# stm32f4discovery-daugherboard-v2.net
KiCad netlist of a schematic drawn in EAGLE
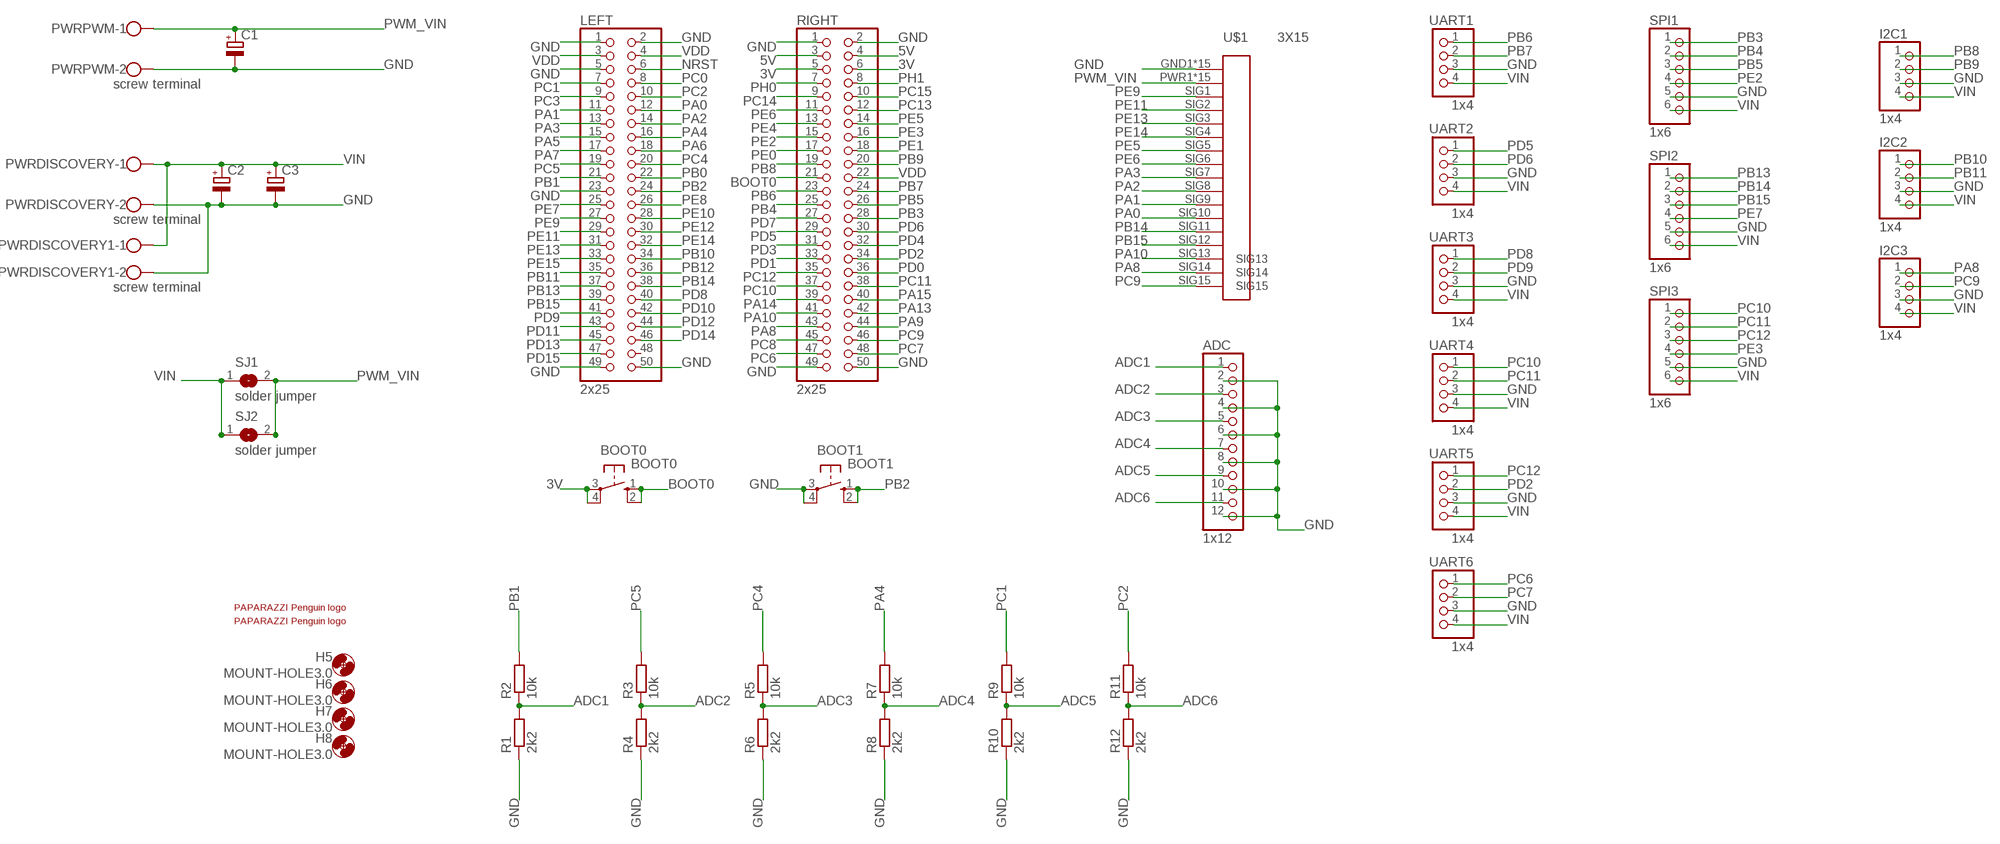
[diagram p0: schematic, sheet 1]

(export (version "E")
  (design (tool "Eeschema 10.0.6"))
  (components
    (comp (ref "ADC")
      (value "1x12")
      (footprint "eagle-import:1X12_90")
      (libsource (lib "eagle-import") (part "PINHD-1X12/90"))
    )
    (comp (ref "BOOT0")
      (value "BOOT0")
      (footprint "eagle-import:B3F-10XX")
      (fields (field (name "MPN") "B3F-1000"))
      (libsource (lib "eagle-import") (part "10-XX"))
    )
    (comp (ref "BOOT1")
      (value "BOOT1")
      (footprint "eagle-import:B3F-10XX")
      (fields (field (name "MPN") "B3F-1000"))
      (libsource (lib "eagle-import") (part "10-XX"))
    )
    (comp (ref "C1")
      (value "CPOL-EU153CLV-0807")
      (footprint "eagle-import:153CLV-0807")
      (libsource (lib "eagle-import") (part "CPOL-EU153CLV-0807"))
    )
    (comp (ref "C2")
      (value "CPOL-EU153CLV-0807")
      (footprint "eagle-import:153CLV-0807")
      (libsource (lib "eagle-import") (part "CPOL-EU153CLV-0807"))
    )
    (comp (ref "C3")
      (value "CPOL-EU153CLV-0807")
      (footprint "eagle-import:153CLV-0807")
      (libsource (lib "eagle-import") (part "CPOL-EU153CLV-0807"))
    )
    (comp (ref "H5")
      (value "MOUNT-HOLE3.0")
      (footprint "eagle-import:3,0")
      (libsource (lib "eagle-import") (part "MOUNT-HOLE3.0"))
    )
    (comp (ref "H6")
      (value "MOUNT-HOLE3.0")
      (footprint "eagle-import:3,0")
      (libsource (lib "eagle-import") (part "MOUNT-HOLE3.0"))
    )
    (comp (ref "H7")
      (value "MOUNT-HOLE3.0")
      (footprint "eagle-import:3,0")
      (libsource (lib "eagle-import") (part "MOUNT-HOLE3.0"))
    )
    (comp (ref "H8")
      (value "MOUNT-HOLE3.0")
      (footprint "eagle-import:3,0")
      (libsource (lib "eagle-import") (part "MOUNT-HOLE3.0"))
    )
    (comp (ref "I2C1")
      (value "1x4")
      (footprint "eagle-import:1X04_90")
      (libsource (lib "eagle-import") (part "PINHD-1X4/90"))
    )
    (comp (ref "I2C2")
      (value "1x4")
      (footprint "eagle-import:1X04_90")
      (libsource (lib "eagle-import") (part "PINHD-1X4/90"))
    )
    (comp (ref "I2C3")
      (value "1x4")
      (footprint "eagle-import:1X04_90")
      (libsource (lib "eagle-import") (part "PINHD-1X4/90"))
    )
    (comp (ref "LEFT")
      (value "2x25")
      (footprint "eagle-import:2X25")
      (libsource (lib "eagle-import") (part "PINHD-2X25"))
    )
    (comp (ref "PWRDISCOVERY")
      (value "screw terminal")
      (footprint "eagle-import:W237-102")
      (fields (field (name "MPN") "237-102"))
      (libsource (lib "eagle-import") (part "W237-102"))
    )
    (comp (ref "PWRDISCOVERY1")
      (value "screw terminal")
      (footprint "eagle-import:W237-102")
      (fields
        (field (name "MPN") "237-102")
        (field (name "MPN_1") "237-102")
        (field (name "OC_FARNELL") "unknown")
        (field (name "OC_NEWARK") "70K9898")
      )
      (libsource (lib "eagle-import") (part "W237-102"))
    )
    (comp (ref "PWRPWM")
      (value "screw terminal")
      (footprint "eagle-import:W237-102")
      (fields (field (name "MPN") "237-102"))
      (libsource (lib "eagle-import") (part "W237-102"))
    )
    (comp (ref "R1")
      (value "2k2")
      (footprint "eagle-import:M0805")
      (libsource (lib "eagle-import") (part "R-EU_M0805"))
    )
    (comp (ref "R2")
      (value "10k")
      (footprint "eagle-import:M0805")
      (libsource (lib "eagle-import") (part "R-EU_M0805"))
    )
    (comp (ref "R3")
      (value "10k")
      (footprint "eagle-import:M0805")
      (libsource (lib "eagle-import") (part "R-EU_M0805"))
    )
    (comp (ref "R4")
      (value "2k2")
      (footprint "eagle-import:M0805")
      (libsource (lib "eagle-import") (part "R-EU_M0805"))
    )
    (comp (ref "R5")
      (value "10k")
      (footprint "eagle-import:M0805")
      (libsource (lib "eagle-import") (part "R-EU_M0805"))
    )
    (comp (ref "R6")
      (value "2k2")
      (footprint "eagle-import:M0805")
      (libsource (lib "eagle-import") (part "R-EU_M0805"))
    )
    (comp (ref "R7")
      (value "10k")
      (footprint "eagle-import:M0805")
      (libsource (lib "eagle-import") (part "R-EU_M0805"))
    )
    (comp (ref "R8")
      (value "2k2")
      (footprint "eagle-import:M0805")
      (libsource (lib "eagle-import") (part "R-EU_M0805"))
    )
    (comp (ref "R9")
      (value "10k")
      (footprint "eagle-import:M0805")
      (libsource (lib "eagle-import") (part "R-EU_M0805"))
    )
    (comp (ref "R10")
      (value "2k2")
      (footprint "eagle-import:M0805")
      (libsource (lib "eagle-import") (part "R-EU_M0805"))
    )
    (comp (ref "R11")
      (value "10k")
      (footprint "eagle-import:M0805")
      (libsource (lib "eagle-import") (part "R-EU_M0805"))
    )
    (comp (ref "R12")
      (value "2k2")
      (footprint "eagle-import:M0805")
      (libsource (lib "eagle-import") (part "R-EU_M0805"))
    )
    (comp (ref "RIGHT")
      (value "2x25")
      (footprint "eagle-import:2X25")
      (libsource (lib "eagle-import") (part "PINHD-2X25"))
    )
    (comp (ref "SJ1")
      (value "solder jumper")
      (footprint "eagle-import:SJW")
      (libsource (lib "eagle-import") (part "SJW"))
    )
    (comp (ref "SJ2")
      (value "solder jumper")
      (footprint "eagle-import:SJW")
      (libsource (lib "eagle-import") (part "SJW"))
    )
    (comp (ref "SPI1")
      (value "1x6")
      (footprint "eagle-import:1X06_90")
      (libsource (lib "eagle-import") (part "PINHD-1X6/90"))
    )
    (comp (ref "SPI2")
      (value "1x6")
      (footprint "eagle-import:1X06_90")
      (libsource (lib "eagle-import") (part "PINHD-1X6/90"))
    )
    (comp (ref "SPI3")
      (value "1x6")
      (footprint "eagle-import:1X06_90")
      (libsource (lib "eagle-import") (part "PINHD-1X6/90"))
    )
    (comp (ref "U$1")
      (value "3X15")
      (footprint "eagle-import:3X15")
      (libsource (lib "eagle-import") (part "3X15"))
    )
    (comp (ref "U$2")
      (value "PAPARAZZI")
      (footprint "eagle-import:PAPARAZZI")
      (libsource (lib "eagle-import") (part "PAPARAZZI"))
    )
    (comp (ref "U$3")
      (value "PAPARAZZI")
      (footprint "eagle-import:PAPARAZZI")
      (libsource (lib "eagle-import") (part "PAPARAZZI"))
    )
    (comp (ref "UART1")
      (value "1x4")
      (footprint "eagle-import:1X04_90")
      (libsource (lib "eagle-import") (part "PINHD-1X4/90"))
    )
    (comp (ref "UART2")
      (value "1x4")
      (footprint "eagle-import:1X04_90")
      (libsource (lib "eagle-import") (part "PINHD-1X4/90"))
    )
    (comp (ref "UART3")
      (value "1x4")
      (footprint "eagle-import:1X04_90")
      (libsource (lib "eagle-import") (part "PINHD-1X4/90"))
    )
    (comp (ref "UART4")
      (value "1x4")
      (footprint "eagle-import:1X04_90")
      (libsource (lib "eagle-import") (part "PINHD-1X4/90"))
    )
    (comp (ref "UART5")
      (value "1x4")
      (footprint "eagle-import:1X04_90")
      (libsource (lib "eagle-import") (part "PINHD-1X4/90"))
    )
    (comp (ref "UART6")
      (value "1x4")
      (footprint "eagle-import:1X04_90")
      (libsource (lib "eagle-import") (part "PINHD-1X4/90"))
    )
  )
  (nets
    (net (code "1") (name "/3V") (class "Default")
      (node (ref "BOOT0") (pin "3") (pinfunction "P_3") (pintype "passive"))
      (node (ref "BOOT0") (pin "4") (pinfunction "P1_4") (pintype "passive"))
      (node (ref "RIGHT") (pin "5") (pinfunction "5_5") (pintype "passive"))
      (node (ref "RIGHT") (pin "6") (pinfunction "6_6") (pintype "passive"))
    )
    (net (code "2") (name "/5V") (class "Default")
      (node (ref "RIGHT") (pin "3") (pinfunction "3_3") (pintype "passive"))
      (node (ref "RIGHT") (pin "4") (pinfunction "4_4") (pintype "passive"))
    )
    (net (code "3") (name "/ADC1") (class "Default")
      (node (ref "ADC") (pin "1") (pinfunction "1_1") (pintype "passive"))
      (node (ref "R1") (pin "2") (pinfunction "2_2") (pintype "passive"))
      (node (ref "R2") (pin "1") (pinfunction "1_1") (pintype "passive"))
    )
    (net (code "4") (name "/ADC2") (class "Default")
      (node (ref "ADC") (pin "3") (pinfunction "3_3") (pintype "passive"))
      (node (ref "R3") (pin "1") (pinfunction "1_1") (pintype "passive"))
      (node (ref "R4") (pin "2") (pinfunction "2_2") (pintype "passive"))
    )
    (net (code "5") (name "/ADC3") (class "Default")
      (node (ref "ADC") (pin "5") (pinfunction "5_5") (pintype "passive"))
      (node (ref "R5") (pin "1") (pinfunction "1_1") (pintype "passive"))
      (node (ref "R6") (pin "2") (pinfunction "2_2") (pintype "passive"))
    )
    (net (code "6") (name "/ADC4") (class "Default")
      (node (ref "ADC") (pin "7") (pinfunction "7_7") (pintype "passive"))
      (node (ref "R7") (pin "1") (pinfunction "1_1") (pintype "passive"))
      (node (ref "R8") (pin "2") (pinfunction "2_2") (pintype "passive"))
    )
    (net (code "7") (name "/ADC5") (class "Default")
      (node (ref "ADC") (pin "9") (pinfunction "9_9") (pintype "passive"))
      (node (ref "R10") (pin "2") (pinfunction "2_2") (pintype "passive"))
      (node (ref "R9") (pin "1") (pinfunction "1_1") (pintype "passive"))
    )
    (net (code "8") (name "/ADC6") (class "Default")
      (node (ref "ADC") (pin "11") (pinfunction "11_11") (pintype "passive"))
      (node (ref "R11") (pin "1") (pinfunction "1_1") (pintype "passive"))
      (node (ref "R12") (pin "2") (pinfunction "2_2") (pintype "passive"))
    )
    (net (code "9") (name "/BOOT0") (class "Default")
      (node (ref "BOOT0") (pin "1") (pinfunction "S_1") (pintype "passive"))
      (node (ref "BOOT0") (pin "2") (pinfunction "S1_2") (pintype "passive"))
      (node (ref "RIGHT") (pin "21") (pinfunction "21_21") (pintype "passive"))
    )
    (net (code "10") (name "/GND") (class "Default")
      (node (ref "ADC") (pin "10") (pinfunction "10_10") (pintype "passive"))
      (node (ref "ADC") (pin "12") (pinfunction "12_12") (pintype "passive"))
      (node (ref "ADC") (pin "2") (pinfunction "2_2") (pintype "passive"))
      (node (ref "ADC") (pin "4") (pinfunction "4_4") (pintype "passive"))
      (node (ref "ADC") (pin "6") (pinfunction "6_6") (pintype "passive"))
      (node (ref "ADC") (pin "8") (pinfunction "8_8") (pintype "passive"))
      (node (ref "BOOT1") (pin "3") (pinfunction "P_3") (pintype "passive"))
      (node (ref "BOOT1") (pin "4") (pinfunction "P1_4") (pintype "passive"))
      (node (ref "C1") (pin "-") (pinfunction "-_-") (pintype "passive"))
      (node (ref "C2") (pin "-") (pinfunction "-_-") (pintype "passive"))
      (node (ref "C3") (pin "-") (pinfunction "-_-") (pintype "passive"))
      (node (ref "I2C1") (pin "3") (pinfunction "3_3") (pintype "passive"))
      (node (ref "I2C2") (pin "3") (pinfunction "3_3") (pintype "passive"))
      (node (ref "I2C3") (pin "3") (pinfunction "3_3") (pintype "passive"))
      (node (ref "LEFT") (pin "1") (pinfunction "1_1") (pintype "passive"))
      (node (ref "LEFT") (pin "2") (pinfunction "2_2") (pintype "passive"))
      (node (ref "LEFT") (pin "23") (pinfunction "23_23") (pintype "passive"))
      (node (ref "LEFT") (pin "49") (pinfunction "49_49") (pintype "passive"))
      (node (ref "LEFT") (pin "5") (pinfunction "5_5") (pintype "passive"))
      (node (ref "LEFT") (pin "50") (pinfunction "50_50") (pintype "passive"))
      (node (ref "PWRDISCOVERY") (pin "2") (pinfunction "KL_2") (pintype "passive"))
      (node (ref "PWRDISCOVERY1") (pin "2") (pinfunction "KL_2") (pintype "passive"))
      (node (ref "PWRPWM") (pin "2") (pinfunction "KL_2") (pintype "passive"))
      (node (ref "R1") (pin "1") (pinfunction "1_1") (pintype "passive"))
      (node (ref "R10") (pin "1") (pinfunction "1_1") (pintype "passive"))
      (node (ref "R12") (pin "1") (pinfunction "1_1") (pintype "passive"))
      (node (ref "R4") (pin "1") (pinfunction "1_1") (pintype "passive"))
      (node (ref "R6") (pin "1") (pinfunction "1_1") (pintype "passive"))
      (node (ref "R8") (pin "1") (pinfunction "1_1") (pintype "passive"))
      (node (ref "RIGHT") (pin "1") (pinfunction "1_1") (pintype "passive"))
      (node (ref "RIGHT") (pin "2") (pinfunction "2_2") (pintype "passive"))
      (node (ref "RIGHT") (pin "49") (pinfunction "49_49") (pintype "passive"))
      (node (ref "RIGHT") (pin "50") (pinfunction "50_50") (pintype "passive"))
      (node (ref "SPI1") (pin "5") (pinfunction "5_5") (pintype "passive"))
      (node (ref "SPI2") (pin "5") (pinfunction "5_5") (pintype "passive"))
      (node (ref "SPI3") (pin "5") (pinfunction "5_5") (pintype "passive"))
      (node (ref "U$1") (pin "GND1") (pinfunction "GND_GND1") (pintype "bidirectional"))
      (node (ref "U$1") (pin "GND10") (pinfunction "GND_GND10") (pintype "bidirectional"))
      (node (ref "U$1") (pin "GND11") (pinfunction "GND_GND11") (pintype "bidirectional"))
      (node (ref "U$1") (pin "GND12") (pinfunction "GND_GND12") (pintype "bidirectional"))
      (node (ref "U$1") (pin "GND13") (pinfunction "GND_GND13") (pintype "bidirectional"))
      (node (ref "U$1") (pin "GND14") (pinfunction "GND_GND14") (pintype "bidirectional"))
      (node (ref "U$1") (pin "GND15") (pinfunction "GND_GND15") (pintype "bidirectional"))
      (node (ref "U$1") (pin "GND2") (pinfunction "GND_GND2") (pintype "bidirectional"))
      (node (ref "U$1") (pin "GND3") (pinfunction "GND_GND3") (pintype "bidirectional"))
      (node (ref "U$1") (pin "GND4") (pinfunction "GND_GND4") (pintype "bidirectional"))
      (node (ref "U$1") (pin "GND5") (pinfunction "GND_GND5") (pintype "bidirectional"))
      (node (ref "U$1") (pin "GND6") (pinfunction "GND_GND6") (pintype "bidirectional"))
      (node (ref "U$1") (pin "GND7") (pinfunction "GND_GND7") (pintype "bidirectional"))
      (node (ref "U$1") (pin "GND8") (pinfunction "GND_GND8") (pintype "bidirectional"))
      (node (ref "U$1") (pin "GND9") (pinfunction "GND_GND9") (pintype "bidirectional"))
      (node (ref "UART1") (pin "3") (pinfunction "3_3") (pintype "passive"))
      (node (ref "UART2") (pin "3") (pinfunction "3_3") (pintype "passive"))
      (node (ref "UART3") (pin "3") (pinfunction "3_3") (pintype "passive"))
      (node (ref "UART4") (pin "3") (pinfunction "3_3") (pintype "passive"))
      (node (ref "UART5") (pin "3") (pinfunction "3_3") (pintype "passive"))
      (node (ref "UART6") (pin "3") (pinfunction "3_3") (pintype "passive"))
    )
    (net (code "11") (name "/NRST") (class "Default")
      (node (ref "LEFT") (pin "6") (pinfunction "6_6") (pintype "passive"))
    )
    (net (code "12") (name "/PA0") (class "Default")
      (node (ref "LEFT") (pin "12") (pinfunction "12_12") (pintype "passive"))
      (node (ref "U$1") (pin "SIG10") (pinfunction "SIG10_SIG10") (pintype "bidirectional"))
    )
    (net (code "13") (name "/PA1") (class "Default")
      (node (ref "LEFT") (pin "11") (pinfunction "11_11") (pintype "passive"))
      (node (ref "U$1") (pin "SIG9") (pinfunction "SIG9_SIG9") (pintype "bidirectional"))
    )
    (net (code "14") (name "/PA2") (class "Default")
      (node (ref "LEFT") (pin "14") (pinfunction "14_14") (pintype "passive"))
      (node (ref "U$1") (pin "SIG8") (pinfunction "SIG8_SIG8") (pintype "bidirectional"))
    )
    (net (code "15") (name "/PA3") (class "Default")
      (node (ref "LEFT") (pin "13") (pinfunction "13_13") (pintype "passive"))
      (node (ref "U$1") (pin "SIG7") (pinfunction "SIG7_SIG7") (pintype "bidirectional"))
    )
    (net (code "16") (name "/PA4") (class "Default")
      (node (ref "LEFT") (pin "16") (pinfunction "16_16") (pintype "passive"))
      (node (ref "R7") (pin "2") (pinfunction "2_2") (pintype "passive"))
    )
    (net (code "17") (name "/PA5") (class "Default")
      (node (ref "LEFT") (pin "15") (pinfunction "15_15") (pintype "passive"))
    )
    (net (code "18") (name "/PA6") (class "Default")
      (node (ref "LEFT") (pin "18") (pinfunction "18_18") (pintype "passive"))
    )
    (net (code "19") (name "/PA7") (class "Default")
      (node (ref "LEFT") (pin "17") (pinfunction "17_17") (pintype "passive"))
    )
    (net (code "20") (name "/PA8") (class "Default")
      (node (ref "I2C3") (pin "1") (pinfunction "1_1") (pintype "passive"))
      (node (ref "RIGHT") (pin "43") (pinfunction "43_43") (pintype "passive"))
      (node (ref "U$1") (pin "SIG14") (pinfunction "SIG14_SIG14") (pintype "bidirectional"))
    )
    (net (code "21") (name "/PA9") (class "Default")
      (node (ref "RIGHT") (pin "44") (pinfunction "44_44") (pintype "passive"))
    )
    (net (code "22") (name "/PA10") (class "Default")
      (node (ref "RIGHT") (pin "41") (pinfunction "41_41") (pintype "passive"))
      (node (ref "U$1") (pin "SIG13") (pinfunction "SIG13_SIG13") (pintype "bidirectional"))
    )
    (net (code "23") (name "/PA13") (class "Default")
      (node (ref "RIGHT") (pin "42") (pinfunction "42_42") (pintype "passive"))
    )
    (net (code "24") (name "/PA14") (class "Default")
      (node (ref "RIGHT") (pin "39") (pinfunction "39_39") (pintype "passive"))
    )
    (net (code "25") (name "/PA15") (class "Default")
      (node (ref "RIGHT") (pin "40") (pinfunction "40_40") (pintype "passive"))
    )
    (net (code "26") (name "/PB0") (class "Default")
      (node (ref "LEFT") (pin "22") (pinfunction "22_22") (pintype "passive"))
    )
    (net (code "27") (name "/PB1") (class "Default")
      (node (ref "LEFT") (pin "21") (pinfunction "21_21") (pintype "passive"))
      (node (ref "R2") (pin "2") (pinfunction "2_2") (pintype "passive"))
    )
    (net (code "28") (name "/PB2") (class "Default")
      (node (ref "BOOT1") (pin "1") (pinfunction "S_1") (pintype "passive"))
      (node (ref "BOOT1") (pin "2") (pinfunction "S1_2") (pintype "passive"))
      (node (ref "LEFT") (pin "24") (pinfunction "24_24") (pintype "passive"))
    )
    (net (code "29") (name "/PB3") (class "Default")
      (node (ref "RIGHT") (pin "28") (pinfunction "28_28") (pintype "passive"))
      (node (ref "SPI1") (pin "1") (pinfunction "1_1") (pintype "passive"))
    )
    (net (code "30") (name "/PB4") (class "Default")
      (node (ref "RIGHT") (pin "25") (pinfunction "25_25") (pintype "passive"))
      (node (ref "SPI1") (pin "2") (pinfunction "2_2") (pintype "passive"))
    )
    (net (code "31") (name "/PB5") (class "Default")
      (node (ref "RIGHT") (pin "26") (pinfunction "26_26") (pintype "passive"))
      (node (ref "SPI1") (pin "3") (pinfunction "3_3") (pintype "passive"))
    )
    (net (code "32") (name "/PB6") (class "Default")
      (node (ref "RIGHT") (pin "23") (pinfunction "23_23") (pintype "passive"))
      (node (ref "UART1") (pin "1") (pinfunction "1_1") (pintype "passive"))
    )
    (net (code "33") (name "/PB7") (class "Default")
      (node (ref "RIGHT") (pin "24") (pinfunction "24_24") (pintype "passive"))
      (node (ref "UART1") (pin "2") (pinfunction "2_2") (pintype "passive"))
    )
    (net (code "34") (name "/PB8") (class "Default")
      (node (ref "I2C1") (pin "1") (pinfunction "1_1") (pintype "passive"))
      (node (ref "RIGHT") (pin "19") (pinfunction "19_19") (pintype "passive"))
    )
    (net (code "35") (name "/PB9") (class "Default")
      (node (ref "I2C1") (pin "2") (pinfunction "2_2") (pintype "passive"))
      (node (ref "RIGHT") (pin "20") (pinfunction "20_20") (pintype "passive"))
    )
    (net (code "36") (name "/PB10") (class "Default")
      (node (ref "I2C2") (pin "1") (pinfunction "1_1") (pintype "passive"))
      (node (ref "LEFT") (pin "34") (pinfunction "34_34") (pintype "passive"))
    )
    (net (code "37") (name "/PB11") (class "Default")
      (node (ref "I2C2") (pin "2") (pinfunction "2_2") (pintype "passive"))
      (node (ref "LEFT") (pin "35") (pinfunction "35_35") (pintype "passive"))
    )
    (net (code "38") (name "/PB12") (class "Default")
      (node (ref "LEFT") (pin "36") (pinfunction "36_36") (pintype "passive"))
    )
    (net (code "39") (name "/PB13") (class "Default")
      (node (ref "LEFT") (pin "37") (pinfunction "37_37") (pintype "passive"))
      (node (ref "SPI2") (pin "1") (pinfunction "1_1") (pintype "passive"))
    )
    (net (code "40") (name "/PB14") (class "Default")
      (node (ref "LEFT") (pin "38") (pinfunction "38_38") (pintype "passive"))
      (node (ref "SPI2") (pin "2") (pinfunction "2_2") (pintype "passive"))
      (node (ref "U$1") (pin "SIG11") (pinfunction "SIG11_SIG11") (pintype "bidirectional"))
    )
    (net (code "41") (name "/PB15") (class "Default")
      (node (ref "LEFT") (pin "39") (pinfunction "39_39") (pintype "passive"))
      (node (ref "SPI2") (pin "3") (pinfunction "3_3") (pintype "passive"))
      (node (ref "U$1") (pin "SIG12") (pinfunction "SIG12_SIG12") (pintype "bidirectional"))
    )
    (net (code "42") (name "/PC0") (class "Default")
      (node (ref "LEFT") (pin "8") (pinfunction "8_8") (pintype "passive"))
    )
    (net (code "43") (name "/PC1") (class "Default")
      (node (ref "LEFT") (pin "7") (pinfunction "7_7") (pintype "passive"))
      (node (ref "R9") (pin "2") (pinfunction "2_2") (pintype "passive"))
    )
    (net (code "44") (name "/PC2") (class "Default")
      (node (ref "LEFT") (pin "10") (pinfunction "10_10") (pintype "passive"))
      (node (ref "R11") (pin "2") (pinfunction "2_2") (pintype "passive"))
    )
    (net (code "45") (name "/PC3") (class "Default")
      (node (ref "LEFT") (pin "9") (pinfunction "9_9") (pintype "passive"))
    )
    (net (code "46") (name "/PC4") (class "Default")
      (node (ref "LEFT") (pin "20") (pinfunction "20_20") (pintype "passive"))
      (node (ref "R5") (pin "2") (pinfunction "2_2") (pintype "passive"))
    )
    (net (code "47") (name "/PC5") (class "Default")
      (node (ref "LEFT") (pin "19") (pinfunction "19_19") (pintype "passive"))
      (node (ref "R3") (pin "2") (pinfunction "2_2") (pintype "passive"))
    )
    (net (code "48") (name "/PC6") (class "Default")
      (node (ref "RIGHT") (pin "47") (pinfunction "47_47") (pintype "passive"))
      (node (ref "UART6") (pin "1") (pinfunction "1_1") (pintype "passive"))
    )
    (net (code "49") (name "/PC7") (class "Default")
      (node (ref "RIGHT") (pin "48") (pinfunction "48_48") (pintype "passive"))
      (node (ref "UART6") (pin "2") (pinfunction "2_2") (pintype "passive"))
    )
    (net (code "50") (name "/PC8") (class "Default")
      (node (ref "RIGHT") (pin "45") (pinfunction "45_45") (pintype "passive"))
    )
    (net (code "51") (name "/PC9") (class "Default")
      (node (ref "I2C3") (pin "2") (pinfunction "2_2") (pintype "passive"))
      (node (ref "RIGHT") (pin "46") (pinfunction "46_46") (pintype "passive"))
      (node (ref "U$1") (pin "SIG15") (pinfunction "SIG15_SIG15") (pintype "bidirectional"))
    )
    (net (code "52") (name "/PC10") (class "Default")
      (node (ref "RIGHT") (pin "37") (pinfunction "37_37") (pintype "passive"))
      (node (ref "SPI3") (pin "1") (pinfunction "1_1") (pintype "passive"))
      (node (ref "UART4") (pin "1") (pinfunction "1_1") (pintype "passive"))
    )
    (net (code "53") (name "/PC11") (class "Default")
      (node (ref "RIGHT") (pin "38") (pinfunction "38_38") (pintype "passive"))
      (node (ref "SPI3") (pin "2") (pinfunction "2_2") (pintype "passive"))
      (node (ref "UART4") (pin "2") (pinfunction "2_2") (pintype "passive"))
    )
    (net (code "54") (name "/PC12") (class "Default")
      (node (ref "RIGHT") (pin "35") (pinfunction "35_35") (pintype "passive"))
      (node (ref "SPI3") (pin "3") (pinfunction "3_3") (pintype "passive"))
      (node (ref "UART5") (pin "1") (pinfunction "1_1") (pintype "passive"))
    )
    (net (code "55") (name "/PC13") (class "Default")
      (node (ref "RIGHT") (pin "12") (pinfunction "12_12") (pintype "passive"))
    )
    (net (code "56") (name "/PC14") (class "Default")
      (node (ref "RIGHT") (pin "9") (pinfunction "9_9") (pintype "passive"))
    )
    (net (code "57") (name "/PC15") (class "Default")
      (node (ref "RIGHT") (pin "10") (pinfunction "10_10") (pintype "passive"))
    )
    (net (code "58") (name "/PD0") (class "Default")
      (node (ref "RIGHT") (pin "36") (pinfunction "36_36") (pintype "passive"))
    )
    (net (code "59") (name "/PD1") (class "Default")
      (node (ref "RIGHT") (pin "33") (pinfunction "33_33") (pintype "passive"))
    )
    (net (code "60") (name "/PD2") (class "Default")
      (node (ref "RIGHT") (pin "34") (pinfunction "34_34") (pintype "passive"))
      (node (ref "UART5") (pin "2") (pinfunction "2_2") (pintype "passive"))
    )
    (net (code "61") (name "/PD3") (class "Default")
      (node (ref "RIGHT") (pin "31") (pinfunction "31_31") (pintype "passive"))
    )
    (net (code "62") (name "/PD4") (class "Default")
      (node (ref "RIGHT") (pin "32") (pinfunction "32_32") (pintype "passive"))
    )
    (net (code "63") (name "/PD5") (class "Default")
      (node (ref "RIGHT") (pin "29") (pinfunction "29_29") (pintype "passive"))
      (node (ref "UART2") (pin "1") (pinfunction "1_1") (pintype "passive"))
    )
    (net (code "64") (name "/PD6") (class "Default")
      (node (ref "RIGHT") (pin "30") (pinfunction "30_30") (pintype "passive"))
      (node (ref "UART2") (pin "2") (pinfunction "2_2") (pintype "passive"))
    )
    (net (code "65") (name "/PD7") (class "Default")
      (node (ref "RIGHT") (pin "27") (pinfunction "27_27") (pintype "passive"))
    )
    (net (code "66") (name "/PD8") (class "Default")
      (node (ref "LEFT") (pin "40") (pinfunction "40_40") (pintype "passive"))
      (node (ref "UART3") (pin "1") (pinfunction "1_1") (pintype "passive"))
    )
    (net (code "67") (name "/PD9") (class "Default")
      (node (ref "LEFT") (pin "41") (pinfunction "41_41") (pintype "passive"))
      (node (ref "UART3") (pin "2") (pinfunction "2_2") (pintype "passive"))
    )
    (net (code "68") (name "/PD10") (class "Default")
      (node (ref "LEFT") (pin "42") (pinfunction "42_42") (pintype "passive"))
    )
    (net (code "69") (name "/PD11") (class "Default")
      (node (ref "LEFT") (pin "43") (pinfunction "43_43") (pintype "passive"))
    )
    (net (code "70") (name "/PD12") (class "Default")
      (node (ref "LEFT") (pin "44") (pinfunction "44_44") (pintype "passive"))
    )
    (net (code "71") (name "/PD13") (class "Default")
      (node (ref "LEFT") (pin "45") (pinfunction "45_45") (pintype "passive"))
    )
    (net (code "72") (name "/PD14") (class "Default")
      (node (ref "LEFT") (pin "46") (pinfunction "46_46") (pintype "passive"))
    )
    (net (code "73") (name "/PD15") (class "Default")
      (node (ref "LEFT") (pin "47") (pinfunction "47_47") (pintype "passive"))
    )
    (net (code "74") (name "/PE0") (class "Default")
      (node (ref "RIGHT") (pin "17") (pinfunction "17_17") (pintype "passive"))
    )
    (net (code "75") (name "/PE1") (class "Default")
      (node (ref "RIGHT") (pin "18") (pinfunction "18_18") (pintype "passive"))
    )
    (net (code "76") (name "/PE2") (class "Default")
      (node (ref "RIGHT") (pin "15") (pinfunction "15_15") (pintype "passive"))
      (node (ref "SPI1") (pin "4") (pinfunction "4_4") (pintype "passive"))
    )
    (net (code "77") (name "/PE3") (class "Default")
      (node (ref "RIGHT") (pin "16") (pinfunction "16_16") (pintype "passive"))
      (node (ref "SPI3") (pin "4") (pinfunction "4_4") (pintype "passive"))
    )
    (net (code "78") (name "/PE4") (class "Default")
      (node (ref "RIGHT") (pin "13") (pinfunction "13_13") (pintype "passive"))
    )
    (net (code "79") (name "/PE5") (class "Default")
      (node (ref "RIGHT") (pin "14") (pinfunction "14_14") (pintype "passive"))
      (node (ref "U$1") (pin "SIG5") (pinfunction "SIG5_SIG5") (pintype "bidirectional"))
    )
    (net (code "80") (name "/PE6") (class "Default")
      (node (ref "RIGHT") (pin "11") (pinfunction "11_11") (pintype "passive"))
      (node (ref "U$1") (pin "SIG6") (pinfunction "SIG6_SIG6") (pintype "bidirectional"))
    )
    (net (code "81") (name "/PE7") (class "Default")
      (node (ref "LEFT") (pin "25") (pinfunction "25_25") (pintype "passive"))
      (node (ref "SPI2") (pin "4") (pinfunction "4_4") (pintype "passive"))
    )
    (net (code "82") (name "/PE8") (class "Default")
      (node (ref "LEFT") (pin "26") (pinfunction "26_26") (pintype "passive"))
    )
    (net (code "83") (name "/PE9") (class "Default")
      (node (ref "LEFT") (pin "27") (pinfunction "27_27") (pintype "passive"))
      (node (ref "U$1") (pin "SIG1") (pinfunction "SIG1_SIG1") (pintype "bidirectional"))
    )
    (net (code "84") (name "/PE10") (class "Default")
      (node (ref "LEFT") (pin "28") (pinfunction "28_28") (pintype "passive"))
    )
    (net (code "85") (name "/PE11") (class "Default")
      (node (ref "LEFT") (pin "29") (pinfunction "29_29") (pintype "passive"))
      (node (ref "U$1") (pin "SIG2") (pinfunction "SIG2_SIG2") (pintype "bidirectional"))
    )
    (net (code "86") (name "/PE12") (class "Default")
      (node (ref "LEFT") (pin "30") (pinfunction "30_30") (pintype "passive"))
    )
    (net (code "87") (name "/PE13") (class "Default")
      (node (ref "LEFT") (pin "31") (pinfunction "31_31") (pintype "passive"))
      (node (ref "U$1") (pin "SIG3") (pinfunction "SIG3_SIG3") (pintype "bidirectional"))
    )
    (net (code "88") (name "/PE14") (class "Default")
      (node (ref "LEFT") (pin "32") (pinfunction "32_32") (pintype "passive"))
      (node (ref "U$1") (pin "SIG4") (pinfunction "SIG4_SIG4") (pintype "bidirectional"))
    )
    (net (code "89") (name "/PE15") (class "Default")
      (node (ref "LEFT") (pin "33") (pinfunction "33_33") (pintype "passive"))
    )
    (net (code "90") (name "/PH0") (class "Default")
      (node (ref "RIGHT") (pin "7") (pinfunction "7_7") (pintype "passive"))
    )
    (net (code "91") (name "/PH1") (class "Default")
      (node (ref "RIGHT") (pin "8") (pinfunction "8_8") (pintype "passive"))
    )
    (net (code "92") (name "/PWM_VIN") (class "Default")
      (node (ref "C1") (pin "+") (pinfunction "+_+") (pintype "passive"))
      (node (ref "PWRPWM") (pin "1") (pinfunction "KL_1") (pintype "passive"))
      (node (ref "SJ1") (pin "2") (pinfunction "2_2") (pintype "passive"))
      (node (ref "SJ2") (pin "2") (pinfunction "2_2") (pintype "passive"))
      (node (ref "U$1") (pin "PWR1") (pinfunction "PWR_PWR1") (pintype "bidirectional"))
      (node (ref "U$1") (pin "PWR10") (pinfunction "PWR_PWR10") (pintype "bidirectional"))
      (node (ref "U$1") (pin "PWR11") (pinfunction "PWR_PWR11") (pintype "bidirectional"))
      (node (ref "U$1") (pin "PWR12") (pinfunction "PWR_PWR12") (pintype "bidirectional"))
      (node (ref "U$1") (pin "PWR13") (pinfunction "PWR_PWR13") (pintype "bidirectional"))
      (node (ref "U$1") (pin "PWR14") (pinfunction "PWR_PWR14") (pintype "bidirectional"))
      (node (ref "U$1") (pin "PWR15") (pinfunction "PWR_PWR15") (pintype "bidirectional"))
      (node (ref "U$1") (pin "PWR2") (pinfunction "PWR_PWR2") (pintype "bidirectional"))
      (node (ref "U$1") (pin "PWR3") (pinfunction "PWR_PWR3") (pintype "bidirectional"))
      (node (ref "U$1") (pin "PWR4") (pinfunction "PWR_PWR4") (pintype "bidirectional"))
      (node (ref "U$1") (pin "PWR5") (pinfunction "PWR_PWR5") (pintype "bidirectional"))
      (node (ref "U$1") (pin "PWR6") (pinfunction "PWR_PWR6") (pintype "bidirectional"))
      (node (ref "U$1") (pin "PWR7") (pinfunction "PWR_PWR7") (pintype "bidirectional"))
      (node (ref "U$1") (pin "PWR8") (pinfunction "PWR_PWR8") (pintype "bidirectional"))
      (node (ref "U$1") (pin "PWR9") (pinfunction "PWR_PWR9") (pintype "bidirectional"))
    )
    (net (code "93") (name "/VDD") (class "Default")
      (node (ref "LEFT") (pin "3") (pinfunction "3_3") (pintype "passive"))
      (node (ref "LEFT") (pin "4") (pinfunction "4_4") (pintype "passive"))
      (node (ref "RIGHT") (pin "22") (pinfunction "22_22") (pintype "passive"))
    )
    (net (code "94") (name "/VIN") (class "Default")
      (node (ref "C2") (pin "+") (pinfunction "+_+") (pintype "passive"))
      (node (ref "C3") (pin "+") (pinfunction "+_+") (pintype "passive"))
      (node (ref "I2C1") (pin "4") (pinfunction "4_4") (pintype "passive"))
      (node (ref "I2C2") (pin "4") (pinfunction "4_4") (pintype "passive"))
      (node (ref "I2C3") (pin "4") (pinfunction "4_4") (pintype "passive"))
      (node (ref "PWRDISCOVERY") (pin "1") (pinfunction "KL_1") (pintype "passive"))
      (node (ref "PWRDISCOVERY1") (pin "1") (pinfunction "KL_1") (pintype "passive"))
      (node (ref "SJ1") (pin "1") (pinfunction "1_1") (pintype "passive"))
      (node (ref "SJ2") (pin "1") (pinfunction "1_1") (pintype "passive"))
      (node (ref "SPI1") (pin "6") (pinfunction "6_6") (pintype "passive"))
      (node (ref "SPI2") (pin "6") (pinfunction "6_6") (pintype "passive"))
      (node (ref "SPI3") (pin "6") (pinfunction "6_6") (pintype "passive"))
      (node (ref "UART1") (pin "4") (pinfunction "4_4") (pintype "passive"))
      (node (ref "UART2") (pin "4") (pinfunction "4_4") (pintype "passive"))
      (node (ref "UART3") (pin "4") (pinfunction "4_4") (pintype "passive"))
      (node (ref "UART4") (pin "4") (pinfunction "4_4") (pintype "passive"))
      (node (ref "UART5") (pin "4") (pinfunction "4_4") (pintype "passive"))
      (node (ref "UART6") (pin "4") (pinfunction "4_4") (pintype "passive"))
    )
    (net (code "95") (name "unconnected-(LEFT-Pad48)") (class "Default")
      (node (ref "LEFT") (pin "48") (pinfunction "48_48") (pintype "passive"))
    )
  )
)
